# PSPS_AVNC_SRD_CS_combined-2021-02-07.net
KiCad netlist of a schematic drawn in EAGLE
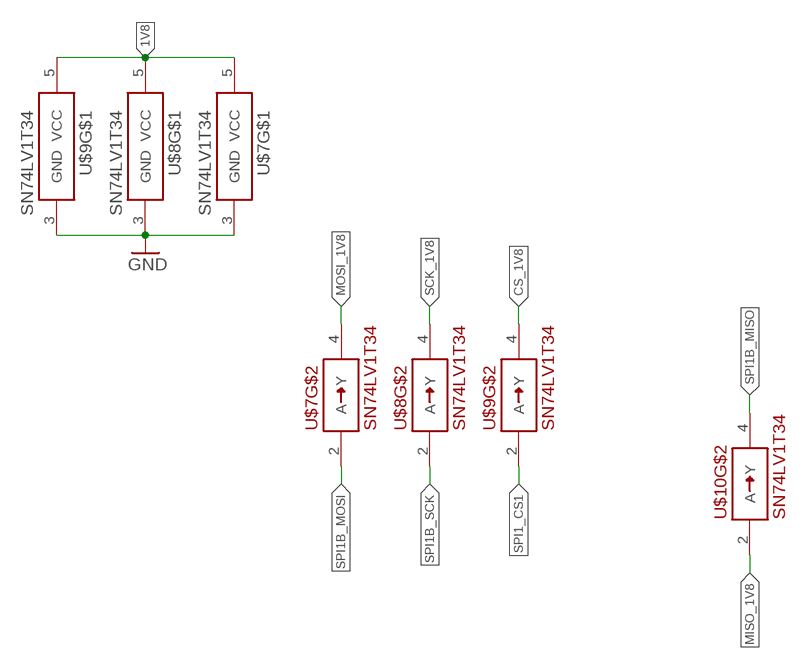
[diagram p0: schematic, sheet 1, part 1 of 2]
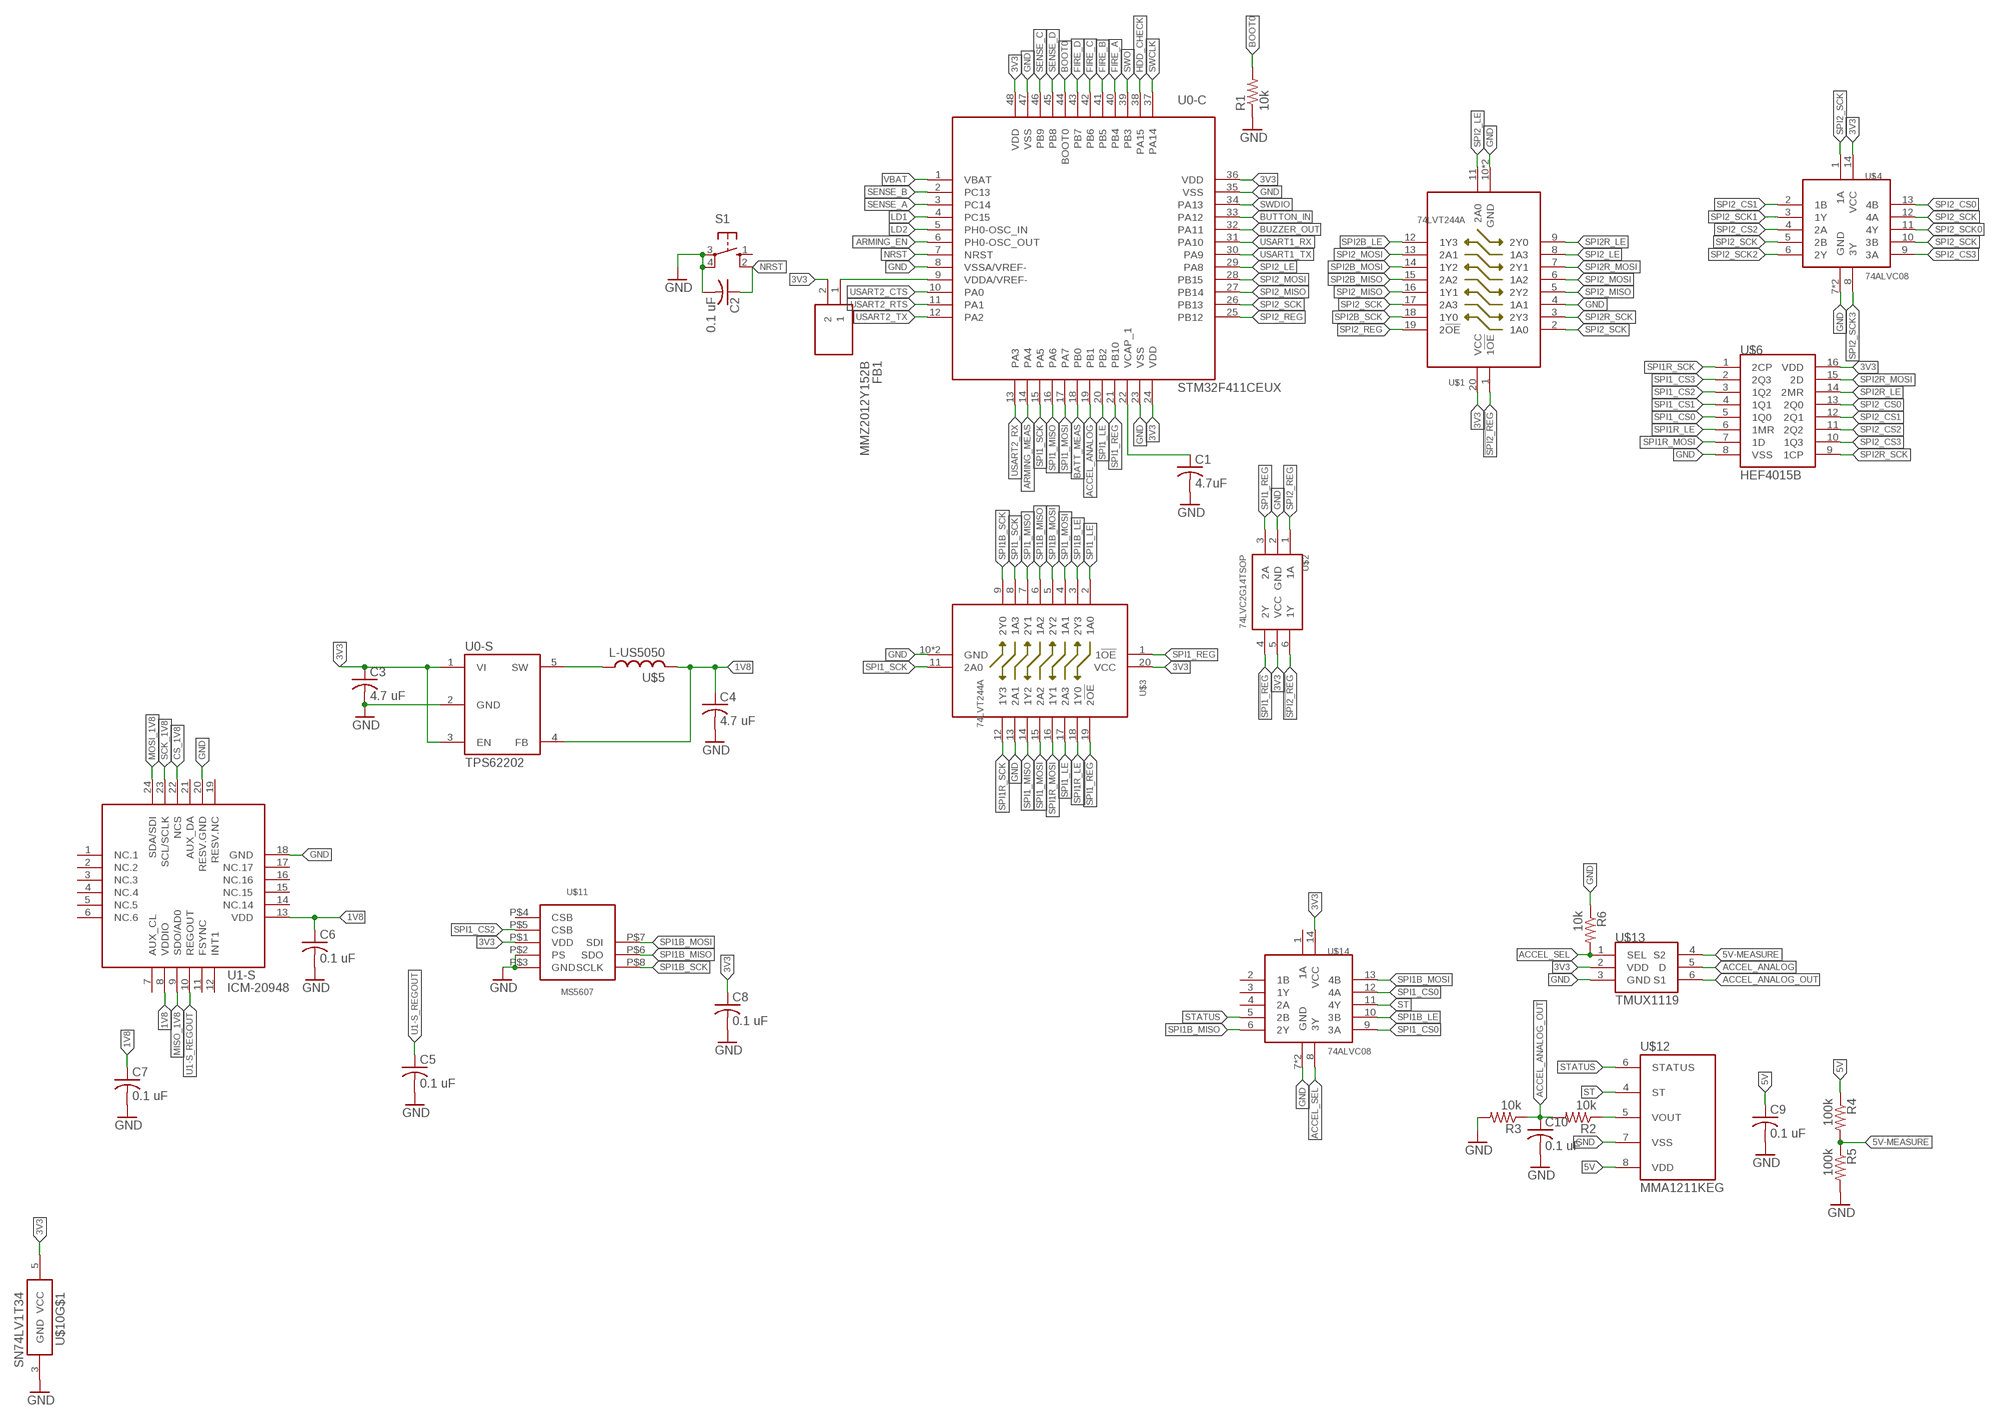
[diagram p1: schematic, sheet 1, part 2 of 2]

(export (version "E")
  (design (tool "Eeschema 10.0.6"))
  (components
    (comp (ref "C1")
      (value "4.7uF")
      (footprint "eagle-import:C0805")
      (libsource (lib "eagle-import") (part "C-USC0805"))
    )
    (comp (ref "C2")
      (value "0.1 uF")
      (footprint "eagle-import:C0805")
      (libsource (lib "eagle-import") (part "C-USC0805"))
    )
    (comp (ref "C3")
      (value "4.7 uF")
      (footprint "eagle-import:C0805")
      (libsource (lib "eagle-import") (part "C-USC0805"))
    )
    (comp (ref "C4")
      (value "4.7 uF")
      (footprint "eagle-import:C0805")
      (libsource (lib "eagle-import") (part "C-USC0805"))
    )
    (comp (ref "C5")
      (value "0.1 uF")
      (footprint "eagle-import:C0805")
      (libsource (lib "eagle-import") (part "C-USC0805"))
    )
    (comp (ref "C6")
      (value "0.1 uF")
      (footprint "eagle-import:C0805")
      (libsource (lib "eagle-import") (part "C-USC0805"))
    )
    (comp (ref "C7")
      (value "0.1 uF")
      (footprint "eagle-import:C0805")
      (libsource (lib "eagle-import") (part "C-USC0805"))
    )
    (comp (ref "C8")
      (value "0.1 uF")
      (footprint "eagle-import:C0805")
      (libsource (lib "eagle-import") (part "C-USC0805"))
    )
    (comp (ref "C9")
      (value "0.1 uF")
      (footprint "eagle-import:C0805")
      (libsource (lib "eagle-import") (part "C-USC0805"))
    )
    (comp (ref "C10")
      (value "0.1 uF")
      (footprint "eagle-import:C0805")
      (libsource (lib "eagle-import") (part "C-USC0805"))
    )
    (comp (ref "FB1")
      (value "MMZ2012Y152B")
      (footprint "eagle-import:BEADC2012X105N")
      (fields (field (name "MOUSER_PART_NUMBER") "810-MMZ2012Y152B"))
      (libsource (lib "eagle-import") (part "MMZ2012Y152B"))
    )
    (comp (ref "R1")
      (value "10k")
      (footprint "eagle-import:M0805")
      (libsource (lib "eagle-import") (part "R-US_M0805"))
    )
    (comp (ref "R2")
      (value "10k")
      (footprint "eagle-import:M0805")
      (libsource (lib "eagle-import") (part "R-US_M0805"))
    )
    (comp (ref "R3")
      (value "10k")
      (footprint "eagle-import:M0805")
      (libsource (lib "eagle-import") (part "R-US_M0805"))
    )
    (comp (ref "R4")
      (value "100k")
      (footprint "eagle-import:M0805")
      (libsource (lib "eagle-import") (part "R-US_M0805"))
    )
    (comp (ref "R5")
      (value "100k")
      (footprint "eagle-import:M0805")
      (libsource (lib "eagle-import") (part "R-US_M0805"))
    )
    (comp (ref "R6")
      (value "10k")
      (footprint "eagle-import:M0805")
      (libsource (lib "eagle-import") (part "R-US_M0805"))
    )
    (comp (ref "S1")
      (value "10-XX")
      (footprint "eagle-import:B3F-10XX")
      (fields (field (name "MPN") "B3F-1000"))
      (libsource (lib "eagle-import") (part "10-XX"))
    )
    (comp (ref "U$1")
      (value "74LVT244A")
      (footprint "eagle-import:QFN50P450X250X100-21T300X100N")
      (libsource (lib "eagle-import") (part "74LVT244A"))
    )
    (comp (ref "U$2")
      (value "74LVC2G14TSOP")
      (footprint "eagle-import:SOP95P280X110-6N")
      (libsource (lib "eagle-import") (part "74LVC2G14TSOP"))
    )
    (comp (ref "U$3")
      (value "74LVT244A")
      (footprint "eagle-import:QFN50P450X250X100-21T300X100N")
      (libsource (lib "eagle-import") (part "74LVT244A"))
    )
    (comp (ref "U$4")
      (value "74ALVC08")
      (footprint "eagle-import:QFN50P300X250X100-15T150X100N")
      (libsource (lib "eagle-import") (part "74ALVC08"))
    )
    (comp (ref "U$5")
      (value "L-US5050")
      (footprint "eagle-import:INDDFN1250X1250X600-2N")
      (libsource (lib "eagle-import") (part "L-US5050"))
    )
    (comp (ref "U$6")
      (value "HEF4015B")
      (footprint "eagle-import:SOIC127P600X265-16N")
      (libsource (lib "eagle-import") (part "HEF4015B"))
    )
    (comp (ref "U$7")
      (value "SN74LV1T34")
      (footprint "eagle-import:SOT65P210X110-5")
      (libsource (lib "eagle-import") (part "SN74LV1T34"))
    )
    (comp (ref "U$8")
      (value "SN74LV1T34")
      (footprint "eagle-import:SOT65P210X110-5")
      (libsource (lib "eagle-import") (part "SN74LV1T34"))
    )
    (comp (ref "U$9")
      (value "SN74LV1T34")
      (footprint "eagle-import:SOT65P210X110-5")
      (libsource (lib "eagle-import") (part "SN74LV1T34"))
    )
    (comp (ref "U$10")
      (value "SN74LV1T34")
      (footprint "eagle-import:SOT65P210X110-5")
      (libsource (lib "eagle-import") (part "SN74LV1T34"))
    )
    (comp (ref "U$11")
      (value "MS5607")
      (footprint "eagle-import:MS5607")
      (libsource (lib "eagle-import") (part "MS5607"))
    )
    (comp (ref "U$12")
      (value "MMA1211KEG")
      (footprint "eagle-import:SOIC127P1041X355-16N")
      (libsource (lib "eagle-import") (part "MMA1211KEG"))
    )
    (comp (ref "U$13")
      (value "TMUX1119")
      (footprint "eagle-import:SOP95P280X145-6N")
      (libsource (lib "eagle-import") (part "TMUX1119"))
    )
    (comp (ref "U$14")
      (value "74ALVC08")
      (footprint "eagle-import:QFN50P300X250X100-15T150X100N")
      (libsource (lib "eagle-import") (part "74ALVC08"))
    )
    (comp (ref "U0-C")
      (value "STM32F411CEUX")
      (footprint "eagle-import:QFN50P700X700X50-49T560N")
      (libsource (lib "eagle-import") (part "STM32F411CEUX"))
    )
    (comp (ref "U0-S")
      (value "TPS62202")
      (footprint "eagle-import:SOT95P280X145-5")
      (libsource (lib "eagle-import") (part "TPS62202"))
    )
    (comp (ref "U1-S")
      (value "ICM-20948")
      (footprint "eagle-import:QFN40P300X300X105-25T159X175")
      (libsource (lib "eagle-import") (part "ICM-20948"))
    )
  )
  (nets
    (net (code "1") (name "/~{SPI1_REG}") (class "Default")
      (node (ref "U$2") (pin "4") (pinfunction "2Y_4") (pintype "bidirectional"))
      (node (ref "U$3") (pin "19") (pinfunction "2~{OE}_19") (pintype "bidirectional"))
    )
    (net (code "2") (name "/~{SPI2_REG}") (class "Default")
      (node (ref "U$1") (pin "1") (pinfunction "1~{OE}_1") (pintype "bidirectional"))
      (node (ref "U$2") (pin "6") (pinfunction "1Y_6") (pintype "bidirectional"))
    )
    (net (code "3") (name "1V8") (class "Default")
      (node (ref "C4") (pin "1") (pinfunction "1_1") (pintype "passive"))
      (node (ref "C6") (pin "1") (pinfunction "1_1") (pintype "passive"))
      (node (ref "C7") (pin "1") (pinfunction "1_1") (pintype "passive"))
      (node (ref "U$5") (pin "2") (pinfunction "2_2") (pintype "passive"))
      (node (ref "U$7") (pin "5") (pinfunction "VCC_5") (pintype "bidirectional"))
      (node (ref "U$8") (pin "5") (pinfunction "VCC_5") (pintype "bidirectional"))
      (node (ref "U$9") (pin "5") (pinfunction "VCC_5") (pintype "bidirectional"))
      (node (ref "U0-S") (pin "4") (pinfunction "FB_4") (pintype "bidirectional"))
      (node (ref "U1-S") (pin "13") (pinfunction "VDD_13") (pintype "bidirectional"))
      (node (ref "U1-S") (pin "8") (pinfunction "VDDIO_8") (pintype "bidirectional"))
    )
    (net (code "4") (name "3V3") (class "Default")
      (node (ref "C3") (pin "1") (pinfunction "1_1") (pintype "passive"))
      (node (ref "C8") (pin "1") (pinfunction "1_1") (pintype "passive"))
      (node (ref "FB1") (pin "2") (pinfunction "2_2") (pintype "bidirectional"))
      (node (ref "U$1") (pin "20") (pinfunction "VCC_20") (pintype "bidirectional"))
      (node (ref "U$10") (pin "5") (pinfunction "VCC_5") (pintype "bidirectional"))
      (node (ref "U$11") (pin "P$1") (pinfunction "VDD_P$1") (pintype "bidirectional"))
      (node (ref "U$13") (pin "2") (pinfunction "VDD_2") (pintype "bidirectional"))
      (node (ref "U$14") (pin "14") (pinfunction "VCC_14") (pintype "bidirectional"))
      (node (ref "U$2") (pin "5") (pinfunction "VCC_5") (pintype "bidirectional"))
      (node (ref "U$3") (pin "20") (pinfunction "VCC_20") (pintype "bidirectional"))
      (node (ref "U$4") (pin "14") (pinfunction "VCC_14") (pintype "bidirectional"))
      (node (ref "U$6") (pin "16") (pinfunction "VDD_16") (pintype "bidirectional"))
      (node (ref "U0-C") (pin "24") (pinfunction "VDD_24") (pintype "bidirectional"))
      (node (ref "U0-C") (pin "36") (pinfunction "VDD_36") (pintype "bidirectional"))
      (node (ref "U0-C") (pin "48") (pinfunction "VDD_48") (pintype "bidirectional"))
      (node (ref "U0-S") (pin "1") (pinfunction "VI_1") (pintype "bidirectional"))
      (node (ref "U0-S") (pin "3") (pinfunction "EN_3") (pintype "bidirectional"))
    )
    (net (code "5") (name "5V") (class "Default")
      (node (ref "C9") (pin "1") (pinfunction "1_1") (pintype "passive"))
      (node (ref "R4") (pin "1") (pinfunction "1_1") (pintype "passive"))
      (node (ref "U$12") (pin "8") (pinfunction "VDD_8") (pintype "bidirectional"))
    )
    (net (code "6") (name "5V-MEASURE") (class "Default")
      (node (ref "R4") (pin "2") (pinfunction "2_2") (pintype "passive"))
      (node (ref "R5") (pin "1") (pinfunction "1_1") (pintype "passive"))
      (node (ref "U$13") (pin "4") (pinfunction "S2_4") (pintype "bidirectional"))
    )
    (net (code "7") (name "ACCEL_ANALOG") (class "Default")
      (node (ref "U$13") (pin "5") (pinfunction "D_5") (pintype "bidirectional"))
      (node (ref "U0-C") (pin "19") (pinfunction "PB1_19") (pintype "bidirectional"))
    )
    (net (code "8") (name "ACCEL_ANALOG_OUT") (class "Default")
      (node (ref "C10") (pin "1") (pinfunction "1_1") (pintype "passive"))
      (node (ref "R2") (pin "2") (pinfunction "2_2") (pintype "passive"))
      (node (ref "R3") (pin "1") (pinfunction "1_1") (pintype "passive"))
      (node (ref "U$13") (pin "6") (pinfunction "S1_6") (pintype "bidirectional"))
    )
    (net (code "9") (name "ACCEL_SEL") (class "Default")
      (node (ref "R6") (pin "2") (pinfunction "2_2") (pintype "passive"))
      (node (ref "U$13") (pin "1") (pinfunction "SEL_1") (pintype "bidirectional"))
      (node (ref "U$14") (pin "8") (pinfunction "3Y_8") (pintype "bidirectional"))
    )
    (net (code "10") (name "ARMING_EN") (class "Default")
      (node (ref "U0-C") (pin "6") (pinfunction "PH0-OSC_OUT_6") (pintype "bidirectional"))
    )
    (net (code "11") (name "ARMING_MEAS") (class "Default")
      (node (ref "U0-C") (pin "14") (pinfunction "PA4_14") (pintype "bidirectional"))
    )
    (net (code "12") (name "BATT_MEAS") (class "Default")
      (node (ref "U0-C") (pin "18") (pinfunction "PB0_18") (pintype "bidirectional"))
    )
    (net (code "13") (name "BOOT0") (class "Default")
      (node (ref "R1") (pin "2") (pinfunction "2_2") (pintype "passive"))
      (node (ref "U0-C") (pin "44") (pinfunction "BOOT0_44") (pintype "bidirectional"))
    )
    (net (code "14") (name "BUTTON_IN") (class "Default")
      (node (ref "U0-C") (pin "33") (pinfunction "PA12_33") (pintype "bidirectional"))
    )
    (net (code "15") (name "BUZZER_OUT") (class "Default")
      (node (ref "U0-C") (pin "32") (pinfunction "PA11_32") (pintype "bidirectional"))
    )
    (net (code "16") (name "CS_1V8") (class "Default")
      (node (ref "U$9") (pin "4") (pinfunction "Y_4") (pintype "bidirectional"))
      (node (ref "U1-S") (pin "22") (pinfunction "NCS_22") (pintype "bidirectional"))
    )
    (net (code "17") (name "FIRE_A") (class "Default")
      (node (ref "U0-C") (pin "40") (pinfunction "PB4_40") (pintype "bidirectional"))
    )
    (net (code "18") (name "FIRE_B") (class "Default")
      (node (ref "U0-C") (pin "41") (pinfunction "PB5_41") (pintype "bidirectional"))
    )
    (net (code "19") (name "FIRE_C") (class "Default")
      (node (ref "U0-C") (pin "42") (pinfunction "PB6_42") (pintype "bidirectional"))
    )
    (net (code "20") (name "FIRE_D") (class "Default")
      (node (ref "U0-C") (pin "43") (pinfunction "PB7_43") (pintype "bidirectional"))
    )
    (net (code "21") (name "GND") (class "Default")
      (node (ref "C1") (pin "2") (pinfunction "2_2") (pintype "passive"))
      (node (ref "C10") (pin "2") (pinfunction "2_2") (pintype "passive"))
      (node (ref "C2") (pin "2") (pinfunction "2_2") (pintype "passive"))
      (node (ref "C3") (pin "2") (pinfunction "2_2") (pintype "passive"))
      (node (ref "C4") (pin "2") (pinfunction "2_2") (pintype "passive"))
      (node (ref "C5") (pin "2") (pinfunction "2_2") (pintype "passive"))
      (node (ref "C6") (pin "2") (pinfunction "2_2") (pintype "passive"))
      (node (ref "C7") (pin "2") (pinfunction "2_2") (pintype "passive"))
      (node (ref "C8") (pin "2") (pinfunction "2_2") (pintype "passive"))
      (node (ref "C9") (pin "2") (pinfunction "2_2") (pintype "passive"))
      (node (ref "R1") (pin "1") (pinfunction "1_1") (pintype "passive"))
      (node (ref "R3") (pin "2") (pinfunction "2_2") (pintype "passive"))
      (node (ref "R5") (pin "2") (pinfunction "2_2") (pintype "passive"))
      (node (ref "R6") (pin "1") (pinfunction "1_1") (pintype "passive"))
      (node (ref "S1") (pin "3") (pinfunction "P_3") (pintype "passive"))
      (node (ref "S1") (pin "4") (pinfunction "P1_4") (pintype "passive"))
      (node (ref "U$1") (pin "10") (pinfunction "GND_10") (pintype "bidirectional"))
      (node (ref "U$1") (pin "21") (pinfunction "GND_21") (pintype "bidirectional"))
      (node (ref "U$1") (pin "4") (pinfunction "1A1_4") (pintype "bidirectional"))
      (node (ref "U$10") (pin "3") (pinfunction "GND_3") (pintype "bidirectional"))
      (node (ref "U$11") (pin "P$2") (pinfunction "PS_P$2") (pintype "bidirectional"))
      (node (ref "U$11") (pin "P$3") (pinfunction "GND_P$3") (pintype "bidirectional"))
      (node (ref "U$12") (pin "7") (pinfunction "VSS_7") (pintype "bidirectional"))
      (node (ref "U$13") (pin "3") (pinfunction "GND_3") (pintype "bidirectional"))
      (node (ref "U$14") (pin "15") (pinfunction "GND_15") (pintype "bidirectional"))
      (node (ref "U$14") (pin "7") (pinfunction "GND_7") (pintype "bidirectional"))
      (node (ref "U$2") (pin "2") (pinfunction "GND_2") (pintype "bidirectional"))
      (node (ref "U$3") (pin "10") (pinfunction "GND_10") (pintype "bidirectional"))
      (node (ref "U$3") (pin "13") (pinfunction "2A1_13") (pintype "bidirectional"))
      (node (ref "U$3") (pin "21") (pinfunction "GND_21") (pintype "bidirectional"))
      (node (ref "U$4") (pin "15") (pinfunction "GND_15") (pintype "bidirectional"))
      (node (ref "U$4") (pin "7") (pinfunction "GND_7") (pintype "bidirectional"))
      (node (ref "U$6") (pin "8") (pinfunction "VSS_8") (pintype "bidirectional"))
      (node (ref "U$7") (pin "3") (pinfunction "GND_3") (pintype "bidirectional"))
      (node (ref "U$8") (pin "3") (pinfunction "GND_3") (pintype "bidirectional"))
      (node (ref "U$9") (pin "3") (pinfunction "GND_3") (pintype "bidirectional"))
      (node (ref "U0-C") (pin "23") (pinfunction "VSS_23") (pintype "bidirectional"))
      (node (ref "U0-C") (pin "35") (pinfunction "VSS_35") (pintype "bidirectional"))
      (node (ref "U0-C") (pin "47") (pinfunction "VSS_47") (pintype "bidirectional"))
      (node (ref "U0-C") (pin "8") (pinfunction "VSSA/VREF-_8") (pintype "bidirectional"))
      (node (ref "U0-S") (pin "2") (pinfunction "GND_2") (pintype "bidirectional"))
      (node (ref "U1-S") (pin "18") (pinfunction "GND_18") (pintype "bidirectional"))
      (node (ref "U1-S") (pin "20") (pinfunction "RESV.GND_20") (pintype "bidirectional"))
    )
    (net (code "22") (name "HDD_CHECK") (class "Default")
      (node (ref "U0-C") (pin "38") (pinfunction "PA15_38") (pintype "bidirectional"))
    )
    (net (code "23") (name "LD1") (class "Default")
      (node (ref "U0-C") (pin "4") (pinfunction "PC15_4") (pintype "bidirectional"))
    )
    (net (code "24") (name "LD2") (class "Default")
      (node (ref "U0-C") (pin "5") (pinfunction "PH0-OSC_IN_5") (pintype "bidirectional"))
    )
    (net (code "25") (name "MISO_1V8") (class "Default")
      (node (ref "U$10") (pin "2") (pinfunction "A_2") (pintype "bidirectional"))
      (node (ref "U1-S") (pin "9") (pinfunction "SDO/AD0_9") (pintype "bidirectional"))
    )
    (net (code "26") (name "MOSI_1V8") (class "Default")
      (node (ref "U$7") (pin "4") (pinfunction "Y_4") (pintype "bidirectional"))
      (node (ref "U1-S") (pin "24") (pinfunction "SDA/SDI_24") (pintype "bidirectional"))
    )
    (net (code "27") (name "NRST") (class "Default")
      (node (ref "C2") (pin "1") (pinfunction "1_1") (pintype "passive"))
      (node (ref "S1") (pin "2") (pinfunction "S1_2") (pintype "passive"))
      (node (ref "U0-C") (pin "7") (pinfunction "NRST_7") (pintype "bidirectional"))
    )
    (net (code "28") (name "Net-(U$12-VOUT)") (class "Default")
      (node (ref "R2") (pin "1") (pinfunction "1_1") (pintype "passive"))
      (node (ref "U$12") (pin "5") (pinfunction "VOUT_5") (pintype "bidirectional"))
    )
    (net (code "29") (name "Net-(U0-C-VCAP_1)") (class "Default")
      (node (ref "C1") (pin "1") (pinfunction "1_1") (pintype "passive"))
      (node (ref "U0-C") (pin "22") (pinfunction "VCAP_1_22") (pintype "bidirectional"))
    )
    (net (code "30") (name "Net-(U0-C-VDDA{slash}VREF-)") (class "Default")
      (node (ref "FB1") (pin "1") (pinfunction "1_1") (pintype "bidirectional"))
      (node (ref "U0-C") (pin "9") (pinfunction "VDDA/VREF-_9") (pintype "bidirectional"))
    )
    (net (code "31") (name "Net-(U0-S-SW)") (class "Default")
      (node (ref "U$5") (pin "1") (pinfunction "1_1") (pintype "passive"))
      (node (ref "U0-S") (pin "5") (pinfunction "SW_5") (pintype "bidirectional"))
    )
    (net (code "32") (name "SCK_1V8") (class "Default")
      (node (ref "U$8") (pin "4") (pinfunction "Y_4") (pintype "bidirectional"))
      (node (ref "U1-S") (pin "23") (pinfunction "SCL/SCLK_23") (pintype "bidirectional"))
    )
    (net (code "33") (name "SENSE_A") (class "Default")
      (node (ref "U0-C") (pin "3") (pinfunction "PC14_3") (pintype "bidirectional"))
    )
    (net (code "34") (name "SENSE_B") (class "Default")
      (node (ref "U0-C") (pin "2") (pinfunction "PC13_2") (pintype "bidirectional"))
    )
    (net (code "35") (name "SENSE_C") (class "Default")
      (node (ref "U0-C") (pin "46") (pinfunction "PB9_46") (pintype "bidirectional"))
    )
    (net (code "36") (name "SENSE_D") (class "Default")
      (node (ref "U0-C") (pin "45") (pinfunction "PB8_45") (pintype "bidirectional"))
    )
    (net (code "37") (name "SPI1B_LE") (class "Default")
      (node (ref "U$14") (pin "10") (pinfunction "3B_10") (pintype "bidirectional"))
      (node (ref "U$3") (pin "3") (pinfunction "2Y3_3") (pintype "bidirectional"))
    )
    (net (code "38") (name "SPI1B_MISO") (class "Default")
      (node (ref "U$10") (pin "4") (pinfunction "Y_4") (pintype "bidirectional"))
      (node (ref "U$11") (pin "P$6") (pinfunction "SDO_P$6") (pintype "bidirectional"))
      (node (ref "U$14") (pin "6") (pinfunction "2Y_6") (pintype "bidirectional"))
      (node (ref "U$3") (pin "6") (pinfunction "1A2_6") (pintype "bidirectional"))
    )
    (net (code "39") (name "SPI1B_MOSI") (class "Default")
      (node (ref "U$11") (pin "P$7") (pinfunction "SDI_P$7") (pintype "bidirectional"))
      (node (ref "U$14") (pin "13") (pinfunction "4B_13") (pintype "bidirectional"))
      (node (ref "U$3") (pin "5") (pinfunction "2Y2_5") (pintype "bidirectional"))
      (node (ref "U$7") (pin "2") (pinfunction "A_2") (pintype "bidirectional"))
    )
    (net (code "40") (name "SPI1B_SCK") (class "Default")
      (node (ref "U$11") (pin "P$8") (pinfunction "SCLK_P$8") (pintype "bidirectional"))
      (node (ref "U$3") (pin "9") (pinfunction "2Y0_9") (pintype "bidirectional"))
      (node (ref "U$8") (pin "2") (pinfunction "A_2") (pintype "bidirectional"))
    )
    (net (code "41") (name "SPI1R_LE") (class "Default")
      (node (ref "U$3") (pin "18") (pinfunction "1Y0_18") (pintype "bidirectional"))
      (node (ref "U$6") (pin "6") (pinfunction "1MR_6") (pintype "bidirectional"))
    )
    (net (code "42") (name "SPI1R_MOSI") (class "Default")
      (node (ref "U$3") (pin "16") (pinfunction "1Y1_16") (pintype "bidirectional"))
      (node (ref "U$6") (pin "7") (pinfunction "1D_7") (pintype "bidirectional"))
    )
    (net (code "43") (name "SPI1R_SCK") (class "Default")
      (node (ref "U$3") (pin "12") (pinfunction "1Y3_12") (pintype "bidirectional"))
      (node (ref "U$6") (pin "1") (pinfunction "2CP_1") (pintype "bidirectional"))
    )
    (net (code "44") (name "SPI1_CS0") (class "Default")
      (node (ref "U$14") (pin "12") (pinfunction "4A_12") (pintype "bidirectional"))
      (node (ref "U$14") (pin "9") (pinfunction "3A_9") (pintype "bidirectional"))
      (node (ref "U$6") (pin "5") (pinfunction "1Q0_5") (pintype "bidirectional"))
    )
    (net (code "45") (name "SPI1_CS1") (class "Default")
      (node (ref "U$6") (pin "4") (pinfunction "1Q1_4") (pintype "bidirectional"))
      (node (ref "U$9") (pin "2") (pinfunction "A_2") (pintype "bidirectional"))
    )
    (net (code "46") (name "SPI1_CS2") (class "Default")
      (node (ref "U$11") (pin "P$5") (pinfunction "CSB_P$5") (pintype "bidirectional"))
      (node (ref "U$6") (pin "3") (pinfunction "1Q2_3") (pintype "bidirectional"))
    )
    (net (code "47") (name "SPI1_CS3") (class "Default")
      (node (ref "U$6") (pin "2") (pinfunction "2Q3_2") (pintype "bidirectional"))
    )
    (net (code "48") (name "SPI1_LE") (class "Default")
      (node (ref "U$3") (pin "17") (pinfunction "2A3_17") (pintype "bidirectional"))
      (node (ref "U$3") (pin "2") (pinfunction "1A0_2") (pintype "bidirectional"))
      (node (ref "U0-C") (pin "20") (pinfunction "PB2_20") (pintype "bidirectional"))
    )
    (net (code "49") (name "SPI1_MISO") (class "Default")
      (node (ref "U$3") (pin "14") (pinfunction "1Y2_14") (pintype "bidirectional"))
      (node (ref "U$3") (pin "7") (pinfunction "2Y1_7") (pintype "bidirectional"))
      (node (ref "U0-C") (pin "16") (pinfunction "PA6_16") (pintype "bidirectional"))
    )
    (net (code "50") (name "SPI1_MOSI") (class "Default")
      (node (ref "U$3") (pin "15") (pinfunction "2A2_15") (pintype "bidirectional"))
      (node (ref "U$3") (pin "4") (pinfunction "1A1_4") (pintype "bidirectional"))
      (node (ref "U0-C") (pin "17") (pinfunction "PA7_17") (pintype "bidirectional"))
    )
    (net (code "51") (name "SPI1_REG") (class "Default")
      (node (ref "U$2") (pin "3") (pinfunction "2A_3") (pintype "bidirectional"))
      (node (ref "U$3") (pin "1") (pinfunction "1~{OE}_1") (pintype "bidirectional"))
      (node (ref "U0-C") (pin "21") (pinfunction "PB10_21") (pintype "bidirectional"))
    )
    (net (code "52") (name "SPI1_SCK") (class "Default")
      (node (ref "U$3") (pin "11") (pinfunction "2A0_11") (pintype "bidirectional"))
      (node (ref "U$3") (pin "8") (pinfunction "1A3_8") (pintype "bidirectional"))
      (node (ref "U0-C") (pin "15") (pinfunction "PA5_15") (pintype "bidirectional"))
    )
    (net (code "53") (name "SPI2B_LE") (class "Default")
      (node (ref "U$1") (pin "12") (pinfunction "1Y3_12") (pintype "bidirectional"))
    )
    (net (code "54") (name "SPI2B_MISO") (class "Default")
      (node (ref "U$1") (pin "15") (pinfunction "2A2_15") (pintype "bidirectional"))
    )
    (net (code "55") (name "SPI2B_MOSI") (class "Default")
      (node (ref "U$1") (pin "14") (pinfunction "1Y2_14") (pintype "bidirectional"))
    )
    (net (code "56") (name "SPI2B_SCK") (class "Default")
      (node (ref "U$1") (pin "18") (pinfunction "1Y0_18") (pintype "bidirectional"))
    )
    (net (code "57") (name "SPI2R_LE") (class "Default")
      (node (ref "U$1") (pin "9") (pinfunction "2Y0_9") (pintype "bidirectional"))
      (node (ref "U$6") (pin "14") (pinfunction "2MR_14") (pintype "bidirectional"))
    )
    (net (code "58") (name "SPI2R_MOSI") (class "Default")
      (node (ref "U$1") (pin "7") (pinfunction "2Y1_7") (pintype "bidirectional"))
      (node (ref "U$6") (pin "15") (pinfunction "2D_15") (pintype "bidirectional"))
    )
    (net (code "59") (name "SPI2R_SCK") (class "Default")
      (node (ref "U$1") (pin "3") (pinfunction "2Y3_3") (pintype "bidirectional"))
      (node (ref "U$6") (pin "9") (pinfunction "1CP_9") (pintype "bidirectional"))
    )
    (net (code "60") (name "SPI2_CS0") (class "Default")
      (node (ref "U$4") (pin "13") (pinfunction "4B_13") (pintype "bidirectional"))
      (node (ref "U$6") (pin "13") (pinfunction "2Q0_13") (pintype "bidirectional"))
    )
    (net (code "61") (name "SPI2_CS1") (class "Default")
      (node (ref "U$4") (pin "2") (pinfunction "1B_2") (pintype "bidirectional"))
      (node (ref "U$6") (pin "12") (pinfunction "2Q1_12") (pintype "bidirectional"))
    )
    (net (code "62") (name "SPI2_CS2") (class "Default")
      (node (ref "U$4") (pin "4") (pinfunction "2A_4") (pintype "bidirectional"))
      (node (ref "U$6") (pin "11") (pinfunction "2Q2_11") (pintype "bidirectional"))
    )
    (net (code "63") (name "SPI2_CS3") (class "Default")
      (node (ref "U$4") (pin "9") (pinfunction "3A_9") (pintype "bidirectional"))
      (node (ref "U$6") (pin "10") (pinfunction "1Q3_10") (pintype "bidirectional"))
    )
    (net (code "64") (name "SPI2_LE") (class "Default")
      (node (ref "U$1") (pin "11") (pinfunction "2A0_11") (pintype "bidirectional"))
      (node (ref "U$1") (pin "8") (pinfunction "1A3_8") (pintype "bidirectional"))
      (node (ref "U0-C") (pin "29") (pinfunction "PA8_29") (pintype "bidirectional"))
    )
    (net (code "65") (name "SPI2_MISO") (class "Default")
      (node (ref "U$1") (pin "16") (pinfunction "1Y1_16") (pintype "bidirectional"))
      (node (ref "U$1") (pin "5") (pinfunction "2Y2_5") (pintype "bidirectional"))
      (node (ref "U0-C") (pin "27") (pinfunction "PB14_27") (pintype "bidirectional"))
    )
    (net (code "66") (name "SPI2_MOSI") (class "Default")
      (node (ref "U$1") (pin "13") (pinfunction "2A1_13") (pintype "bidirectional"))
      (node (ref "U$1") (pin "6") (pinfunction "1A2_6") (pintype "bidirectional"))
      (node (ref "U0-C") (pin "28") (pinfunction "PB15_28") (pintype "bidirectional"))
    )
    (net (code "67") (name "SPI2_REG") (class "Default")
      (node (ref "U$1") (pin "19") (pinfunction "2~{OE}_19") (pintype "bidirectional"))
      (node (ref "U$2") (pin "1") (pinfunction "1A_1") (pintype "bidirectional"))
      (node (ref "U0-C") (pin "25") (pinfunction "PB12_25") (pintype "bidirectional"))
    )
    (net (code "68") (name "SPI2_SCK") (class "Default")
      (node (ref "U$1") (pin "17") (pinfunction "2A3_17") (pintype "bidirectional"))
      (node (ref "U$1") (pin "2") (pinfunction "1A0_2") (pintype "bidirectional"))
      (node (ref "U$4") (pin "1") (pinfunction "1A_1") (pintype "bidirectional"))
      (node (ref "U$4") (pin "10") (pinfunction "3B_10") (pintype "bidirectional"))
      (node (ref "U$4") (pin "12") (pinfunction "4A_12") (pintype "bidirectional"))
      (node (ref "U$4") (pin "5") (pinfunction "2B_5") (pintype "bidirectional"))
      (node (ref "U0-C") (pin "26") (pinfunction "PB13_26") (pintype "bidirectional"))
    )
    (net (code "69") (name "SPI2_SCK0") (class "Default")
      (node (ref "U$4") (pin "11") (pinfunction "4Y_11") (pintype "bidirectional"))
    )
    (net (code "70") (name "SPI2_SCK1") (class "Default")
      (node (ref "U$4") (pin "3") (pinfunction "1Y_3") (pintype "bidirectional"))
    )
    (net (code "71") (name "SPI2_SCK2") (class "Default")
      (node (ref "U$4") (pin "6") (pinfunction "2Y_6") (pintype "bidirectional"))
    )
    (net (code "72") (name "SPI2_SCK3") (class "Default")
      (node (ref "U$4") (pin "8") (pinfunction "3Y_8") (pintype "bidirectional"))
    )
    (net (code "73") (name "ST") (class "Default")
      (node (ref "U$12") (pin "4") (pinfunction "ST_4") (pintype "bidirectional"))
      (node (ref "U$14") (pin "11") (pinfunction "4Y_11") (pintype "bidirectional"))
    )
    (net (code "74") (name "STATUS") (class "Default")
      (node (ref "U$12") (pin "6") (pinfunction "STATUS_6") (pintype "bidirectional"))
      (node (ref "U$14") (pin "5") (pinfunction "2B_5") (pintype "bidirectional"))
    )
    (net (code "75") (name "SWCLK") (class "Default")
      (node (ref "U0-C") (pin "37") (pinfunction "PA14_37") (pintype "bidirectional"))
    )
    (net (code "76") (name "SWDIO") (class "Default")
      (node (ref "U0-C") (pin "34") (pinfunction "PA13_34") (pintype "bidirectional"))
    )
    (net (code "77") (name "SWO") (class "Default")
      (node (ref "U0-C") (pin "39") (pinfunction "PB3_39") (pintype "bidirectional"))
    )
    (net (code "78") (name "U1-S_REGOUT") (class "Default")
      (node (ref "C5") (pin "1") (pinfunction "1_1") (pintype "passive"))
      (node (ref "U1-S") (pin "10") (pinfunction "REGOUT_10") (pintype "bidirectional"))
    )
    (net (code "79") (name "USART1_RX") (class "Default")
      (node (ref "U0-C") (pin "31") (pinfunction "PA10_31") (pintype "bidirectional"))
    )
    (net (code "80") (name "USART1_TX") (class "Default")
      (node (ref "U0-C") (pin "30") (pinfunction "PA9_30") (pintype "bidirectional"))
    )
    (net (code "81") (name "USART2_CTS") (class "Default")
      (node (ref "U0-C") (pin "10") (pinfunction "PA0_10") (pintype "bidirectional"))
    )
    (net (code "82") (name "USART2_RTS") (class "Default")
      (node (ref "U0-C") (pin "11") (pinfunction "PA1_11") (pintype "bidirectional"))
    )
    (net (code "83") (name "USART2_RX") (class "Default")
      (node (ref "U0-C") (pin "13") (pinfunction "PA3_13") (pintype "bidirectional"))
    )
    (net (code "84") (name "USART2_TX") (class "Default")
      (node (ref "U0-C") (pin "12") (pinfunction "PA2_12") (pintype "bidirectional"))
    )
    (net (code "85") (name "VBAT") (class "Default")
      (node (ref "U0-C") (pin "1") (pinfunction "VBAT_1") (pintype "bidirectional"))
    )
    (net (code "86") (name "unconnected-(S1-S-Pad1)") (class "Default")
      (node (ref "S1") (pin "1") (pinfunction "S_1") (pintype "passive"))
    )
    (net (code "87") (name "unconnected-(U$11-CSB-PadP$4)") (class "Default")
      (node (ref "U$11") (pin "P$4") (pinfunction "CSB_P$4") (pintype "bidirectional"))
    )
    (net (code "88") (name "unconnected-(U$14-1A-Pad1)") (class "Default")
      (node (ref "U$14") (pin "1") (pinfunction "1A_1") (pintype "bidirectional"))
    )
    (net (code "89") (name "unconnected-(U$14-1B-Pad2)") (class "Default")
      (node (ref "U$14") (pin "2") (pinfunction "1B_2") (pintype "bidirectional"))
    )
    (net (code "90") (name "unconnected-(U$14-1Y-Pad3)") (class "Default")
      (node (ref "U$14") (pin "3") (pinfunction "1Y_3") (pintype "bidirectional"))
    )
    (net (code "91") (name "unconnected-(U$14-2A-Pad4)") (class "Default")
      (node (ref "U$14") (pin "4") (pinfunction "2A_4") (pintype "bidirectional"))
    )
    (net (code "92") (name "unconnected-(U1-S-AUX_CL-Pad7)") (class "Default")
      (node (ref "U1-S") (pin "7") (pinfunction "AUX_CL_7") (pintype "bidirectional"))
    )
    (net (code "93") (name "unconnected-(U1-S-AUX_DA-Pad21)") (class "Default")
      (node (ref "U1-S") (pin "21") (pinfunction "AUX_DA_21") (pintype "bidirectional"))
    )
    (net (code "94") (name "unconnected-(U1-S-FSYNC-Pad11)") (class "Default")
      (node (ref "U1-S") (pin "11") (pinfunction "FSYNC_11") (pintype "bidirectional"))
    )
    (net (code "95") (name "unconnected-(U1-S-INT1-Pad12)") (class "Default")
      (node (ref "U1-S") (pin "12") (pinfunction "INT1_12") (pintype "bidirectional"))
    )
    (net (code "96") (name "unconnected-(U1-S-NC.1-Pad1)") (class "Default")
      (node (ref "U1-S") (pin "1") (pinfunction "NC.1_1") (pintype "bidirectional"))
    )
    (net (code "97") (name "unconnected-(U1-S-NC.2-Pad2)") (class "Default")
      (node (ref "U1-S") (pin "2") (pinfunction "NC.2_2") (pintype "bidirectional"))
    )
    (net (code "98") (name "unconnected-(U1-S-NC.3-Pad3)") (class "Default")
      (node (ref "U1-S") (pin "3") (pinfunction "NC.3_3") (pintype "bidirectional"))
    )
    (net (code "99") (name "unconnected-(U1-S-NC.4-Pad4)") (class "Default")
      (node (ref "U1-S") (pin "4") (pinfunction "NC.4_4") (pintype "bidirectional"))
    )
    (net (code "100") (name "unconnected-(U1-S-NC.5-Pad5)") (class "Default")
      (node (ref "U1-S") (pin "5") (pinfunction "NC.5_5") (pintype "bidirectional"))
    )
    (net (code "101") (name "unconnected-(U1-S-NC.6-Pad6)") (class "Default")
      (node (ref "U1-S") (pin "6") (pinfunction "NC.6_6") (pintype "bidirectional"))
    )
    (net (code "102") (name "unconnected-(U1-S-NC.14-Pad14)") (class "Default")
      (node (ref "U1-S") (pin "14") (pinfunction "NC.14_14") (pintype "bidirectional"))
    )
    (net (code "103") (name "unconnected-(U1-S-NC.15-Pad15)") (class "Default")
      (node (ref "U1-S") (pin "15") (pinfunction "NC.15_15") (pintype "bidirectional"))
    )
    (net (code "104") (name "unconnected-(U1-S-NC.16-Pad16)") (class "Default")
      (node (ref "U1-S") (pin "16") (pinfunction "NC.16_16") (pintype "bidirectional"))
    )
    (net (code "105") (name "unconnected-(U1-S-NC.17-Pad17)") (class "Default")
      (node (ref "U1-S") (pin "17") (pinfunction "NC.17_17") (pintype "bidirectional"))
    )
    (net (code "106") (name "unconnected-(U1-S-RESV.NC-Pad19)") (class "Default")
      (node (ref "U1-S") (pin "19") (pinfunction "RESV.NC_19") (pintype "bidirectional"))
    )
  )
)
